# vga3.net
KiCad netlist of a schematic drawn in EAGLE
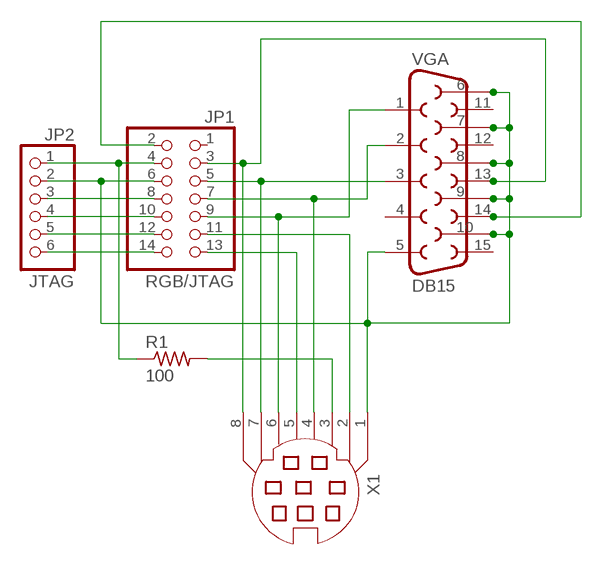
[diagram p0: schematic, sheet 1]

(export (version "E")
  (design (tool "Eeschema 10.0.6"))
  (components
    (comp (ref "JP1")
      (value "RGB/JTAG")
      (footprint "eagle-import:2X07")
      (libsource (lib "eagle-import") (part "PINHD-2X7"))
    )
    (comp (ref "JP2")
      (value "JTAG")
      (footprint "eagle-import:1X06")
      (libsource (lib "eagle-import") (part "PINHD-1X6"))
    )
    (comp (ref "R1")
      (value "100")
      (footprint "eagle-import:0204_7")
      (libsource (lib "eagle-import") (part "R-US_0204/7"))
    )
    (comp (ref "VGA")
      (value "DB15")
      (footprint "eagle-import:DB15")
      (libsource (lib "eagle-import") (part "DB15"))
    )
    (comp (ref "X1")
      (value "MD08S")
      (footprint "eagle-import:MDIN08S")
      (libsource (lib "eagle-import") (part "MD08S"))
    )
  )
  (nets
    (net (code "1") (name "Net-(JP1-Pad2)") (class "Default")
      (node (ref "JP1") (pin "2") (pinfunction "2_2") (pintype "passive"))
      (node (ref "VGA") (pin "14") (pinfunction "14_14") (pintype "passive"))
    )
    (net (code "2") (name "Net-(JP1-Pad3)") (class "Default")
      (node (ref "JP1") (pin "3") (pinfunction "3_3") (pintype "passive"))
      (node (ref "VGA") (pin "13") (pinfunction "13_13") (pintype "passive"))
      (node (ref "X1") (pin "8") (pinfunction "8_8") (pintype "passive"))
    )
    (net (code "3") (name "Net-(JP1-Pad4)") (class "Default")
      (node (ref "JP1") (pin "4") (pinfunction "4_4") (pintype "passive"))
      (node (ref "JP2") (pin "1") (pinfunction "1_1") (pintype "passive"))
      (node (ref "R1") (pin "1") (pinfunction "1_1") (pintype "passive"))
    )
    (net (code "4") (name "Net-(JP1-Pad5)") (class "Default")
      (node (ref "JP1") (pin "5") (pinfunction "5_5") (pintype "passive"))
      (node (ref "VGA") (pin "3") (pinfunction "3_3") (pintype "passive"))
      (node (ref "X1") (pin "7") (pinfunction "7_7") (pintype "passive"))
    )
    (net (code "5") (name "Net-(JP1-Pad6)") (class "Default")
      (node (ref "JP1") (pin "6") (pinfunction "6_6") (pintype "passive"))
      (node (ref "JP2") (pin "2") (pinfunction "2_2") (pintype "passive"))
      (node (ref "VGA") (pin "10") (pinfunction "10_10") (pintype "passive"))
      (node (ref "VGA") (pin "5") (pinfunction "5_5") (pintype "passive"))
      (node (ref "VGA") (pin "6") (pinfunction "6_6") (pintype "passive"))
      (node (ref "VGA") (pin "7") (pinfunction "7_7") (pintype "passive"))
      (node (ref "VGA") (pin "8") (pinfunction "8_8") (pintype "passive"))
      (node (ref "VGA") (pin "9") (pinfunction "9_9") (pintype "passive"))
      (node (ref "X1") (pin "1") (pinfunction "1_1") (pintype "passive"))
    )
    (net (code "6") (name "Net-(JP1-Pad7)") (class "Default")
      (node (ref "JP1") (pin "7") (pinfunction "7_7") (pintype "passive"))
      (node (ref "VGA") (pin "2") (pinfunction "2_2") (pintype "passive"))
      (node (ref "X1") (pin "4") (pinfunction "4_4") (pintype "passive"))
    )
    (net (code "7") (name "Net-(JP1-Pad8)") (class "Default")
      (node (ref "JP1") (pin "8") (pinfunction "8_8") (pintype "passive"))
      (node (ref "JP2") (pin "3") (pinfunction "3_3") (pintype "passive"))
    )
    (net (code "8") (name "Net-(JP1-Pad9)") (class "Default")
      (node (ref "JP1") (pin "9") (pinfunction "9_9") (pintype "passive"))
      (node (ref "VGA") (pin "1") (pinfunction "1_1") (pintype "passive"))
      (node (ref "X1") (pin "6") (pinfunction "6_6") (pintype "passive"))
    )
    (net (code "9") (name "Net-(JP1-Pad10)") (class "Default")
      (node (ref "JP1") (pin "10") (pinfunction "10_10") (pintype "passive"))
      (node (ref "JP2") (pin "4") (pinfunction "4_4") (pintype "passive"))
    )
    (net (code "10") (name "Net-(JP1-Pad11)") (class "Default")
      (node (ref "JP1") (pin "11") (pinfunction "11_11") (pintype "passive"))
      (node (ref "X1") (pin "2") (pinfunction "2_2") (pintype "passive"))
    )
    (net (code "11") (name "Net-(JP1-Pad12)") (class "Default")
      (node (ref "JP1") (pin "12") (pinfunction "12_12") (pintype "passive"))
      (node (ref "JP2") (pin "5") (pinfunction "5_5") (pintype "passive"))
    )
    (net (code "12") (name "Net-(JP1-Pad13)") (class "Default")
      (node (ref "JP1") (pin "13") (pinfunction "13_13") (pintype "passive"))
      (node (ref "X1") (pin "5") (pinfunction "5_5") (pintype "passive"))
    )
    (net (code "13") (name "Net-(JP1-Pad14)") (class "Default")
      (node (ref "JP1") (pin "14") (pinfunction "14_14") (pintype "passive"))
      (node (ref "JP2") (pin "6") (pinfunction "6_6") (pintype "passive"))
    )
    (net (code "14") (name "Net-(R1-Pad2)") (class "Default")
      (node (ref "R1") (pin "2") (pinfunction "2_2") (pintype "passive"))
      (node (ref "X1") (pin "3") (pinfunction "3_3") (pintype "passive"))
    )
    (net (code "15") (name "unconnected-(JP1-Pad1)") (class "Default")
      (node (ref "JP1") (pin "1") (pinfunction "1_1") (pintype "passive"))
    )
    (net (code "16") (name "unconnected-(VGA-Pad4)") (class "Default")
      (node (ref "VGA") (pin "4") (pinfunction "4_4") (pintype "passive"))
    )
    (net (code "17") (name "unconnected-(VGA-Pad11)") (class "Default")
      (node (ref "VGA") (pin "11") (pinfunction "11_11") (pintype "passive"))
    )
    (net (code "18") (name "unconnected-(VGA-Pad12)") (class "Default")
      (node (ref "VGA") (pin "12") (pinfunction "12_12") (pintype "passive"))
    )
    (net (code "19") (name "unconnected-(VGA-Pad15)") (class "Default")
      (node (ref "VGA") (pin "15") (pinfunction "15_15") (pintype "passive"))
    )
  )
)
